# mice_poke_simple_v1_2.net
KiCad netlist of a schematic drawn in EAGLE
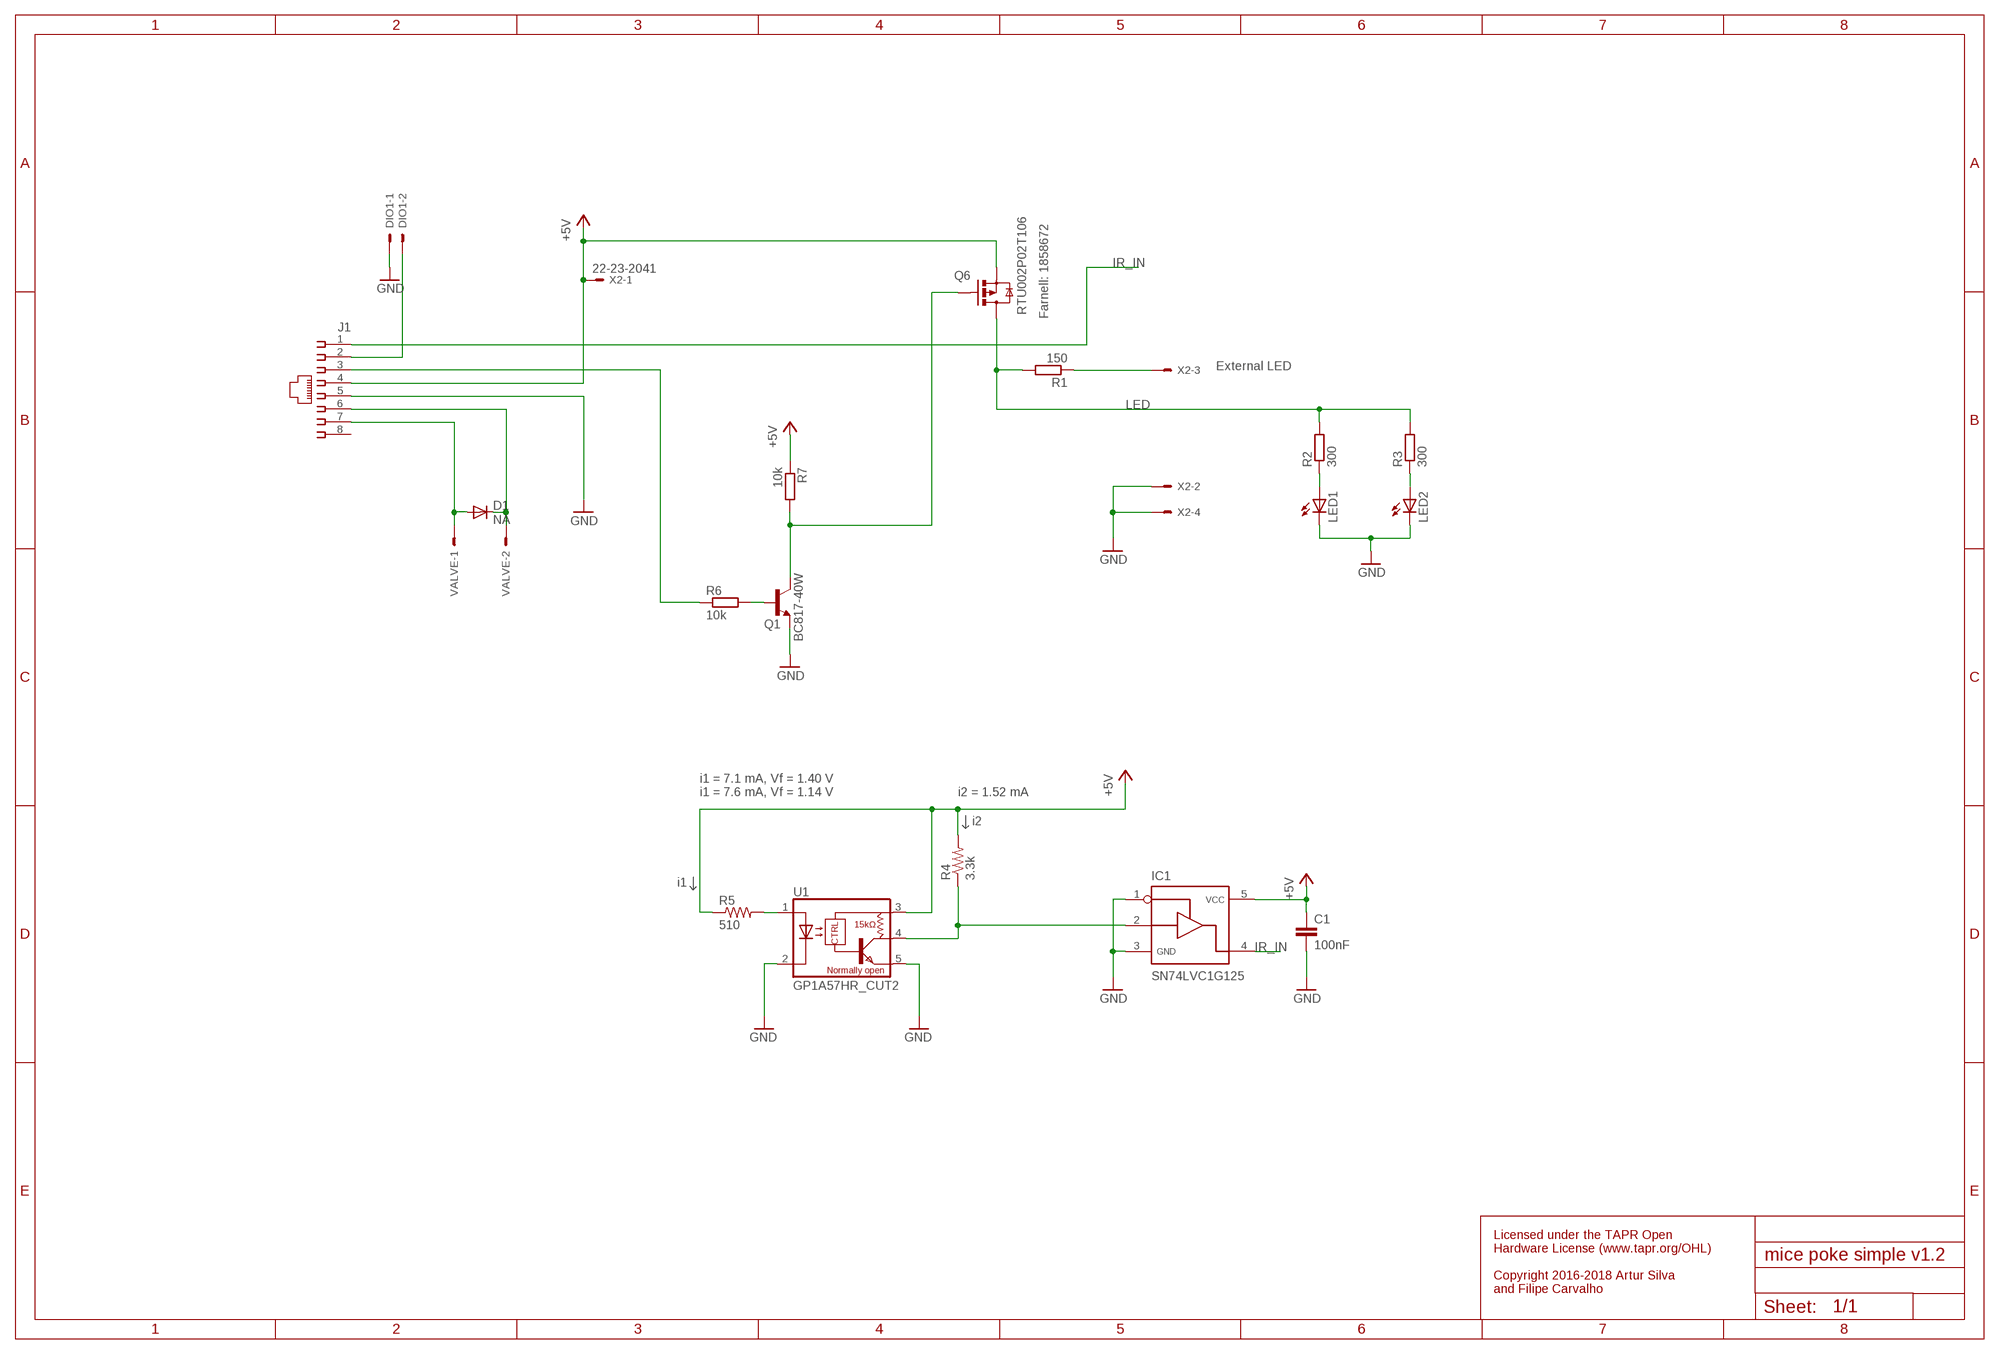
[diagram p0: schematic, sheet 1]

(export (version "E")
  (design (tool "Eeschema 10.0.6"))
  (components
    (comp (ref "C1")
      (value "100nF")
      (footprint "eagle-import:C0402")
      (libsource (lib "eagle-import") (part "C-EUC0402"))
    )
    (comp (ref "D1")
      (value "NA")
      (footprint "eagle-import:SOD323-R")
      (libsource (lib "eagle-import") (part "DIODE-SOD323-R"))
    )
    (comp (ref "DIO1")
      (value "22-23-2021")
      (footprint "eagle-import:22-23-2021")
      (fields (field (name "MF") "MOLEX"))
      (libsource (lib "eagle-import") (part "22-23-2021"))
    )
    (comp (ref "IC1")
      (value "SN74LVC1G125")
      (footprint "eagle-import:SOT23-5")
      (libsource (lib "eagle-import") (part "SN74LVC1G125"))
    )
    (comp (ref "J1")
      (value "215878-2")
      (footprint "eagle-import:215878-2")
      (libsource (lib "eagle-import") (part "215878-2"))
    )
    (comp (ref "LED1")
      (value "LED3MM")
      (footprint "eagle-import:LED3MM")
      (libsource (lib "eagle-import") (part "LED3MM"))
    )
    (comp (ref "LED2")
      (value "LED3MM")
      (footprint "eagle-import:LED3MM")
      (libsource (lib "eagle-import") (part "LED3MM"))
    )
    (comp (ref "Q1")
      (value "BC817-40W")
      (footprint "eagle-import:SOT323-BEC")
      (libsource (lib "eagle-import") (part "BC817"))
    )
    (comp (ref "Q6")
      (value "RTU002P02T106")
      (footprint "eagle-import:SOT323")
      (libsource (lib "eagle-import") (part "MOSFET-PCHANNEL-ROHM"))
    )
    (comp (ref "R1")
      (value "150")
      (footprint "eagle-import:R0402")
      (libsource (lib "eagle-import") (part "R-EU_R0402"))
    )
    (comp (ref "R2")
      (value "300")
      (footprint "eagle-import:R0402")
      (libsource (lib "eagle-import") (part "R-EU_R0402"))
    )
    (comp (ref "R3")
      (value "300")
      (footprint "eagle-import:R0402")
      (libsource (lib "eagle-import") (part "R-EU_R0402"))
    )
    (comp (ref "R4")
      (value "3.3k")
      (footprint "eagle-import:R0402")
      (libsource (lib "eagle-import") (part "R-US_R0402"))
    )
    (comp (ref "R5")
      (value "510")
      (footprint "eagle-import:R0402")
      (libsource (lib "eagle-import") (part "R-US_R0402"))
    )
    (comp (ref "R6")
      (value "10k")
      (footprint "eagle-import:R0402")
      (libsource (lib "eagle-import") (part "R-EU_R0402"))
    )
    (comp (ref "R7")
      (value "10k")
      (footprint "eagle-import:R0402")
      (libsource (lib "eagle-import") (part "R-EU_R0402"))
    )
    (comp (ref "U1")
      (value "GP1A57HR_CUT2")
      (footprint "eagle-import:GP1A57HR_CUT2")
      (libsource (lib "eagle-import") (part "GP1A57HR_CUT2"))
    )
    (comp (ref "VALVE")
      (value "22-23-2021")
      (footprint "eagle-import:22-23-2021")
      (fields (field (name "MF") "MOLEX"))
      (libsource (lib "eagle-import") (part "22-23-2021"))
    )
    (comp (ref "X2")
      (value "22-23-2041")
      (footprint "eagle-import:22-23-2041")
      (fields (field (name "MF") "MOLEX"))
      (libsource (lib "eagle-import") (part "22-23-2041"))
    )
  )
  (nets
    (net (code "1") (name "+5V") (class "Default")
      (node (ref "C1") (pin "1") (pinfunction "1_1") (pintype "passive"))
      (node (ref "IC1") (pin "5") (pinfunction "P$5_5") (pintype "bidirectional"))
      (node (ref "J1") (pin "4") (pinfunction "4_4") (pintype "passive"))
      (node (ref "Q6") (pin "1") (pinfunction "S_1") (pintype "passive"))
      (node (ref "R4") (pin "2") (pinfunction "2_2") (pintype "passive"))
      (node (ref "R5") (pin "1") (pinfunction "1_1") (pintype "passive"))
      (node (ref "R7") (pin "1") (pinfunction "1_1") (pintype "passive"))
      (node (ref "U1") (pin "3") (pinfunction "VCC_3") (pintype "passive"))
      (node (ref "X2") (pin "1") (pinfunction "S_1") (pintype "passive"))
    )
    (net (code "2") (name "/IR_IN") (class "Default")
      (node (ref "IC1") (pin "4") (pinfunction "P$4_4") (pintype "bidirectional"))
      (node (ref "J1") (pin "1") (pinfunction "1_1") (pintype "passive"))
    )
    (net (code "3") (name "/LED") (class "Default")
      (node (ref "Q6") (pin "3") (pinfunction "D_3") (pintype "passive"))
      (node (ref "R1") (pin "2") (pinfunction "2_2") (pintype "passive"))
      (node (ref "R2") (pin "2") (pinfunction "2_2") (pintype "passive"))
      (node (ref "R3") (pin "2") (pinfunction "2_2") (pintype "passive"))
    )
    (net (code "4") (name "GND") (class "Default")
      (node (ref "C1") (pin "2") (pinfunction "2_2") (pintype "passive"))
      (node (ref "DIO1") (pin "1") (pinfunction "S_1") (pintype "passive"))
      (node (ref "IC1") (pin "1") (pinfunction "P$1_1") (pintype "bidirectional"))
      (node (ref "IC1") (pin "3") (pinfunction "P$3_3") (pintype "bidirectional"))
      (node (ref "J1") (pin "5") (pinfunction "5_5") (pintype "passive"))
      (node (ref "LED1") (pin "K") (pinfunction "C_K") (pintype "passive"))
      (node (ref "LED2") (pin "K") (pinfunction "C_K") (pintype "passive"))
      (node (ref "Q1") (pin "E") (pinfunction "E_E") (pintype "passive"))
      (node (ref "U1") (pin "2") (pinfunction "C_2") (pintype "passive"))
      (node (ref "U1") (pin "5") (pinfunction "GND_5") (pintype "passive"))
      (node (ref "X2") (pin "2") (pinfunction "S_2") (pintype "passive"))
      (node (ref "X2") (pin "4") (pinfunction "S_4") (pintype "passive"))
    )
    (net (code "5") (name "Net-(DIO1B-S)") (class "Default")
      (node (ref "DIO1") (pin "2") (pinfunction "S_2") (pintype "passive"))
      (node (ref "J1") (pin "2") (pinfunction "2_2") (pintype "passive"))
    )
    (net (code "6") (name "Net-(IC1-P$2)") (class "Default")
      (node (ref "IC1") (pin "2") (pinfunction "P$2_2") (pintype "bidirectional"))
      (node (ref "R4") (pin "1") (pinfunction "1_1") (pintype "passive"))
      (node (ref "U1") (pin "4") (pinfunction "VO_4") (pintype "passive"))
    )
    (net (code "7") (name "Net-(J1-Pad3)") (class "Default")
      (node (ref "J1") (pin "3") (pinfunction "3_3") (pintype "passive"))
      (node (ref "R6") (pin "1") (pinfunction "1_1") (pintype "passive"))
    )
    (net (code "8") (name "Net-(LED1-PadA)") (class "Default")
      (node (ref "LED1") (pin "A") (pinfunction "A_A") (pintype "passive"))
      (node (ref "R2") (pin "1") (pinfunction "1_1") (pintype "passive"))
    )
    (net (code "9") (name "Net-(LED2-PadA)") (class "Default")
      (node (ref "LED2") (pin "A") (pinfunction "A_A") (pintype "passive"))
      (node (ref "R3") (pin "1") (pinfunction "1_1") (pintype "passive"))
    )
    (net (code "10") (name "Net-(Q1-PadB)") (class "Default")
      (node (ref "Q1") (pin "B") (pinfunction "B_B") (pintype "passive"))
      (node (ref "R6") (pin "2") (pinfunction "2_2") (pintype "passive"))
    )
    (net (code "11") (name "Net-(Q6-G)") (class "Default")
      (node (ref "Q1") (pin "C") (pinfunction "C_C") (pintype "passive"))
      (node (ref "Q6") (pin "2") (pinfunction "G_2") (pintype "passive"))
      (node (ref "R7") (pin "2") (pinfunction "2_2") (pintype "passive"))
    )
    (net (code "12") (name "Net-(U1-A)") (class "Default")
      (node (ref "R5") (pin "2") (pinfunction "2_2") (pintype "passive"))
      (node (ref "U1") (pin "1") (pinfunction "A_1") (pintype "passive"))
    )
    (net (code "13") (name "Net-(VALVEA-S)") (class "Default")
      (node (ref "D1") (pin "A") (pinfunction "A_A") (pintype "passive"))
      (node (ref "J1") (pin "7") (pinfunction "7_7") (pintype "passive"))
      (node (ref "VALVE") (pin "1") (pinfunction "S_1") (pintype "passive"))
    )
    (net (code "14") (name "Net-(VALVEB-S)") (class "Default")
      (node (ref "D1") (pin "C") (pinfunction "C_C") (pintype "passive"))
      (node (ref "J1") (pin "6") (pinfunction "6_6") (pintype "passive"))
      (node (ref "VALVE") (pin "2") (pinfunction "S_2") (pintype "passive"))
    )
    (net (code "15") (name "Net-(X2C-S)") (class "Default")
      (node (ref "R1") (pin "1") (pinfunction "1_1") (pintype "passive"))
      (node (ref "X2") (pin "3") (pinfunction "S_3") (pintype "passive"))
    )
    (net (code "16") (name "unconnected-(J1-Pad8)") (class "Default")
      (node (ref "J1") (pin "8") (pinfunction "8_8") (pintype "passive"))
    )
  )
)
